# 4_Signal_ports_USART_ST-link_Encoder.net
KiCad netlist of a schematic drawn in Altium Designer
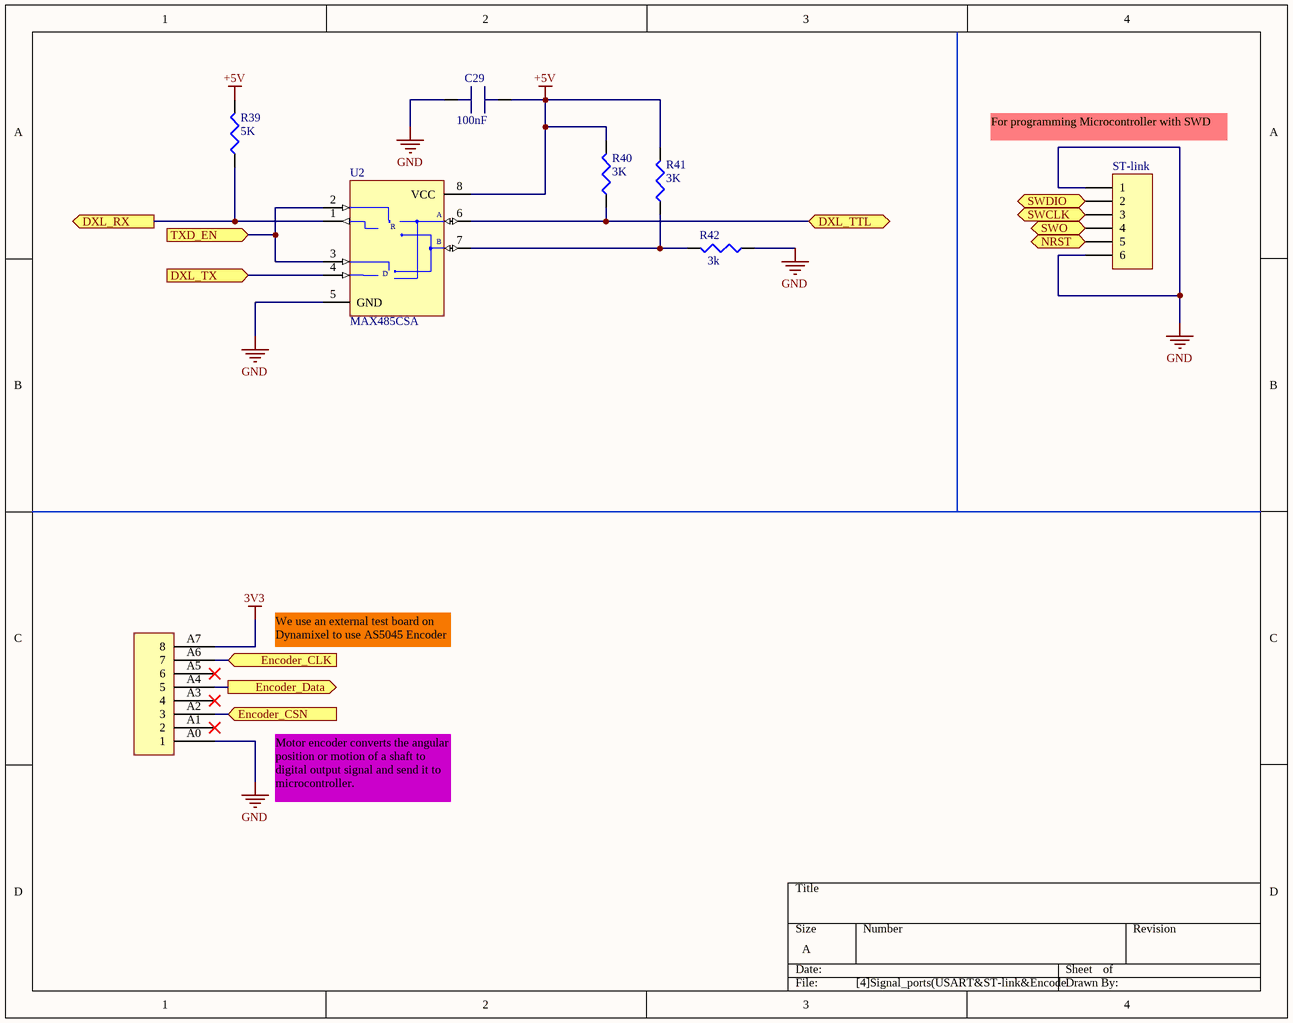
[diagram p0: [4]Signal_ports(USART&ST-link&Encoder).SchDoc]

(export (version "E")
  (design (tool "Eeschema 10.0.6"))
  (components
    (comp (ref "C29") (value "100nF") (footprint "cap_805") (libsource (lib "Driver") (part "cap805")))
    (comp (ref "DXL_Encoder")
      (value "pinheader 8")
      (footprint "PinHeader Female 8")
      (libsource (lib "Pinheader 8 female") (part "pinheader 8"))
    )
    (comp (ref "R39") (value "5K") (footprint "Res805") (libsource (lib "Driver") (part "Res805")))
    (comp (ref "R40") (value "3K") (footprint "Res805") (libsource (lib "Driver") (part "Res805")))
    (comp (ref "R41") (value "3K") (footprint "Res805") (libsource (lib "Driver") (part "Res805")))
    (comp (ref "R42") (value "3k") (footprint "Res805") (libsource (lib "Driver") (part "Res805")))
    (comp (ref "ST-link")
      (value "Molex 22-03-5065")
      (footprint "Molex 22-03-5065")
      (libsource (lib "CM") (part "Molex 22-03-5065"))
    )
    (comp (ref "U2")
      (value "MAX485CSA")
      (footprint "NSO8_N")
      (description "Low-Power, Slew-Rate-Limited RS-485/RS-422 Transceiver")
      (fields (field (name "PUBLISHER") "Altium Limited"))
      (libsource (lib "Maxim Communication Transceiver") (part "MAX485CSA"))
    )
  )
  (nets
    (net (code "1") (name "+5V") (class "Default")
      (node (ref "C29") (pin "2") (pinfunction "2_2") (pintype "passive"))
      (node (ref "R39") (pin "2") (pinfunction "2_2") (pintype "passive"))
      (node (ref "R40") (pin "2") (pinfunction "2_2") (pintype "passive"))
      (node (ref "R41") (pin "2") (pinfunction "2_2") (pintype "passive"))
      (node (ref "U2") (pin "8") (pinfunction "VCC_8") (pintype "power_in"))
    )
    (net (code "2") (name "/DXL_RX") (class "Default")
      (node (ref "R39") (pin "1") (pinfunction "1_1") (pintype "passive"))
      (node (ref "U2") (pin "1") (pinfunction "RO_1") (pintype "output"))
    )
    (net (code "3") (name "/DXL_TTL") (class "Default")
      (node (ref "R40") (pin "1") (pinfunction "1_1") (pintype "passive"))
      (node (ref "U2") (pin "6") (pinfunction "A_6") (pintype "bidirectional"))
    )
    (net (code "4") (name "/DXL_TX") (class "Default")
      (node (ref "U2") (pin "4") (pinfunction "DI_4") (pintype "input"))
    )
    (net (code "5") (name "/Encoder_CLK") (class "Default")
      (node (ref "DXL_Encoder") (pin "A6") (pinfunction "7_A6") (pintype "passive"))
    )
    (net (code "6") (name "/Encoder_CSN") (class "Default")
      (node (ref "DXL_Encoder") (pin "A2") (pinfunction "3_A2") (pintype "passive"))
    )
    (net (code "7") (name "/Encoder_Data") (class "Default")
      (node (ref "DXL_Encoder") (pin "A4") (pinfunction "5_A4") (pintype "passive"))
    )
    (net (code "8") (name "/NRST") (class "Default")
      (node (ref "ST-link") (pin "5") (pinfunction "5_5") (pintype "passive"))
    )
    (net (code "9") (name "/SWCLK") (class "Default")
      (node (ref "ST-link") (pin "3") (pinfunction "3_3") (pintype "passive"))
    )
    (net (code "10") (name "/SWDIO") (class "Default")
      (node (ref "ST-link") (pin "2") (pinfunction "2_2") (pintype "passive"))
    )
    (net (code "11") (name "/SWO") (class "Default")
      (node (ref "ST-link") (pin "4") (pinfunction "4_4") (pintype "passive"))
    )
    (net (code "12") (name "/TXD_EN") (class "Default")
      (node (ref "U2") (pin "2") (pinfunction "~{RE}_2") (pintype "input"))
      (node (ref "U2") (pin "3") (pinfunction "DE_3") (pintype "input"))
    )
    (net (code "13") (name "3V3") (class "Default")
      (node (ref "DXL_Encoder") (pin "A7") (pinfunction "8_A7") (pintype "passive"))
    )
    (net (code "14") (name "GND") (class "Default")
      (node (ref "C29") (pin "1") (pinfunction "1_1") (pintype "passive"))
      (node (ref "DXL_Encoder") (pin "A0") (pinfunction "1_A0") (pintype "passive"))
      (node (ref "R42") (pin "1") (pinfunction "1_1") (pintype "passive"))
      (node (ref "ST-link") (pin "1") (pinfunction "1_1") (pintype "passive"))
      (node (ref "ST-link") (pin "6") (pinfunction "6_6") (pintype "passive"))
      (node (ref "U2") (pin "5") (pinfunction "GND_5") (pintype "power_in"))
    )
    (net (code "15") (name "Net-(U2-B)") (class "Default")
      (node (ref "R41") (pin "1") (pinfunction "1_1") (pintype "passive"))
      (node (ref "R42") (pin "2") (pinfunction "2_2") (pintype "passive"))
      (node (ref "U2") (pin "7") (pinfunction "B_7") (pintype "bidirectional"))
    )
    (net (code "16") (name "unconnected-(DXL_Encoder-2-PadA1)") (class "Default")
      (node (ref "DXL_Encoder") (pin "A1") (pinfunction "2_A1") (pintype "passive+no_connect"))
    )
    (net (code "17") (name "unconnected-(DXL_Encoder-4-PadA3)") (class "Default")
      (node (ref "DXL_Encoder") (pin "A3") (pinfunction "4_A3") (pintype "passive+no_connect"))
    )
    (net (code "18") (name "unconnected-(DXL_Encoder-6-PadA5)") (class "Default")
      (node (ref "DXL_Encoder") (pin "A5") (pinfunction "6_A5") (pintype "passive+no_connect"))
    )
  )
)
